# Mech_Interface_Port_Deployable.net
KiCad netlist of a schematic drawn in Altium Designer
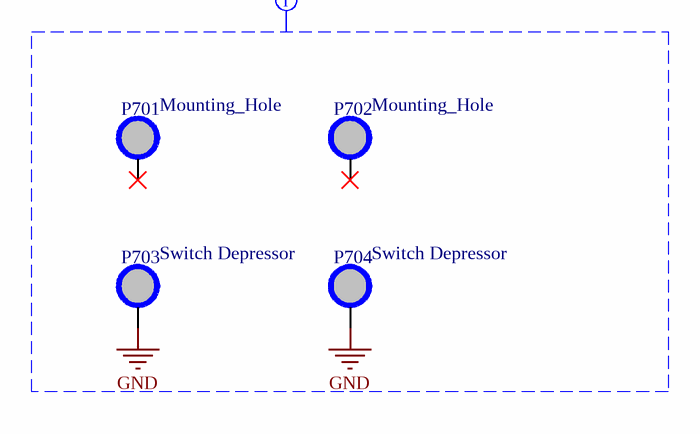
[diagram p0: Mech_Interface_Port_Deployable.SchDoc]

(export (version "E")
  (design (tool "Eeschema 10.0.6"))
  (components
    (comp (ref "P701")
      (value "Mounting_Hole")
      (footprint "DepHinge_Mounting_Hole")
      (description "Depolyable Hinge Mounting hole.")
      (fields (field (name "PART NUMBER") "PXX-ABS-00003") (field (name "PUBLISHER") "AlbertaSat"))
      (libsource (lib "Database") (part "Mounting_Hole"))
    )
    (comp (ref "P702")
      (value "Mounting_Hole")
      (footprint "DepHinge_Mounting_Hole")
      (description "Depolyable Hinge Mounting hole.")
      (fields (field (name "PART NUMBER") "PXX-ABS-00003") (field (name "PUBLISHER") "AlbertaSat"))
      (libsource (lib "Database") (part "Mounting_Hole"))
    )
    (comp (ref "P703")
      (value "Switch Depressor")
      (footprint "Switch_Depressor")
      (description "Hardware for depressing the switch")
      (fields
        (field (name "PART NUMBER") "PXX-ABS-00005")
        (field (name "MANUFACTURER PART NUMBER") "Custom")
        (field (name "PUBLISHER") "AlbertaSat")
      )
      (libsource (lib "Database") (part "Mounting_Hole"))
    )
    (comp (ref "P704")
      (value "Switch Depressor")
      (footprint "Switch_Depressor")
      (description "Hardware for depressing the switch")
      (fields
        (field (name "PART NUMBER") "PXX-ABS-00005")
        (field (name "MANUFACTURER PART NUMBER") "Custom")
        (field (name "PUBLISHER") "AlbertaSat")
      )
      (libsource (lib "Database") (part "Mounting_Hole"))
    )
  )
  (nets
    (net (code "1") (name "GND") (class "Default")
      (node (ref "P703") (pin "1") (pinfunction "0_1") (pintype "passive"))
      (node (ref "P704") (pin "1") (pinfunction "0_1") (pintype "passive"))
    )
    (net (code "2") (name "unconnected-(P701-0-Pad1)") (class "Default")
      (node (ref "P701") (pin "1") (pinfunction "0_1") (pintype "passive+no_connect"))
    )
    (net (code "3") (name "unconnected-(P702-0-Pad1)") (class "Default")
      (node (ref "P702") (pin "1") (pinfunction "0_1") (pintype "passive+no_connect"))
    )
  )
)
